# biosignal-daq-v1_0.net
KiCad netlist of a schematic drawn in EAGLE
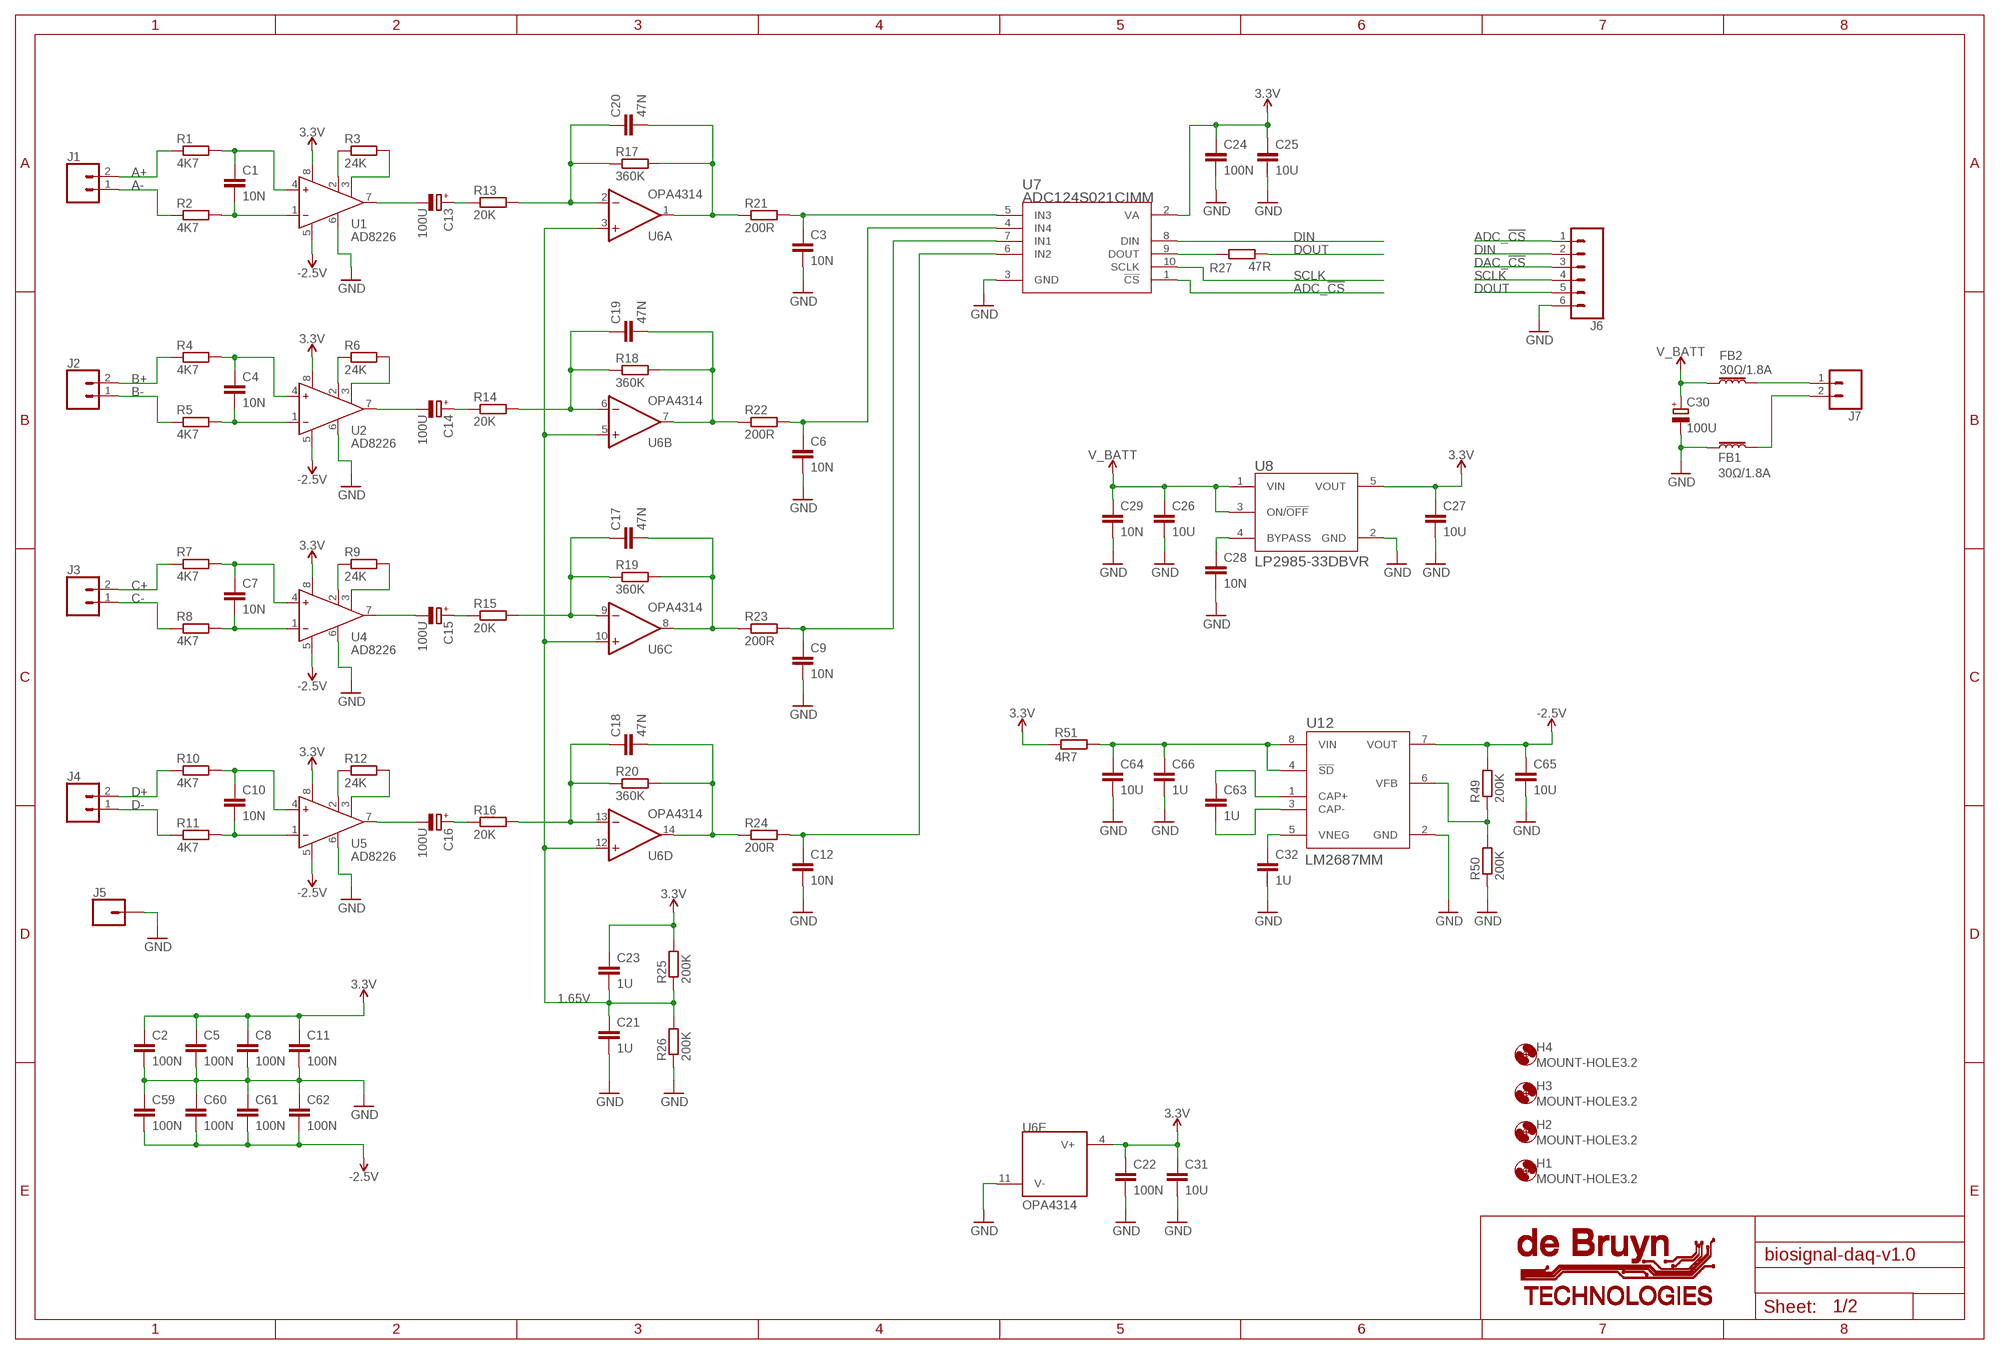
[diagram p0: schematic, sheet 1]
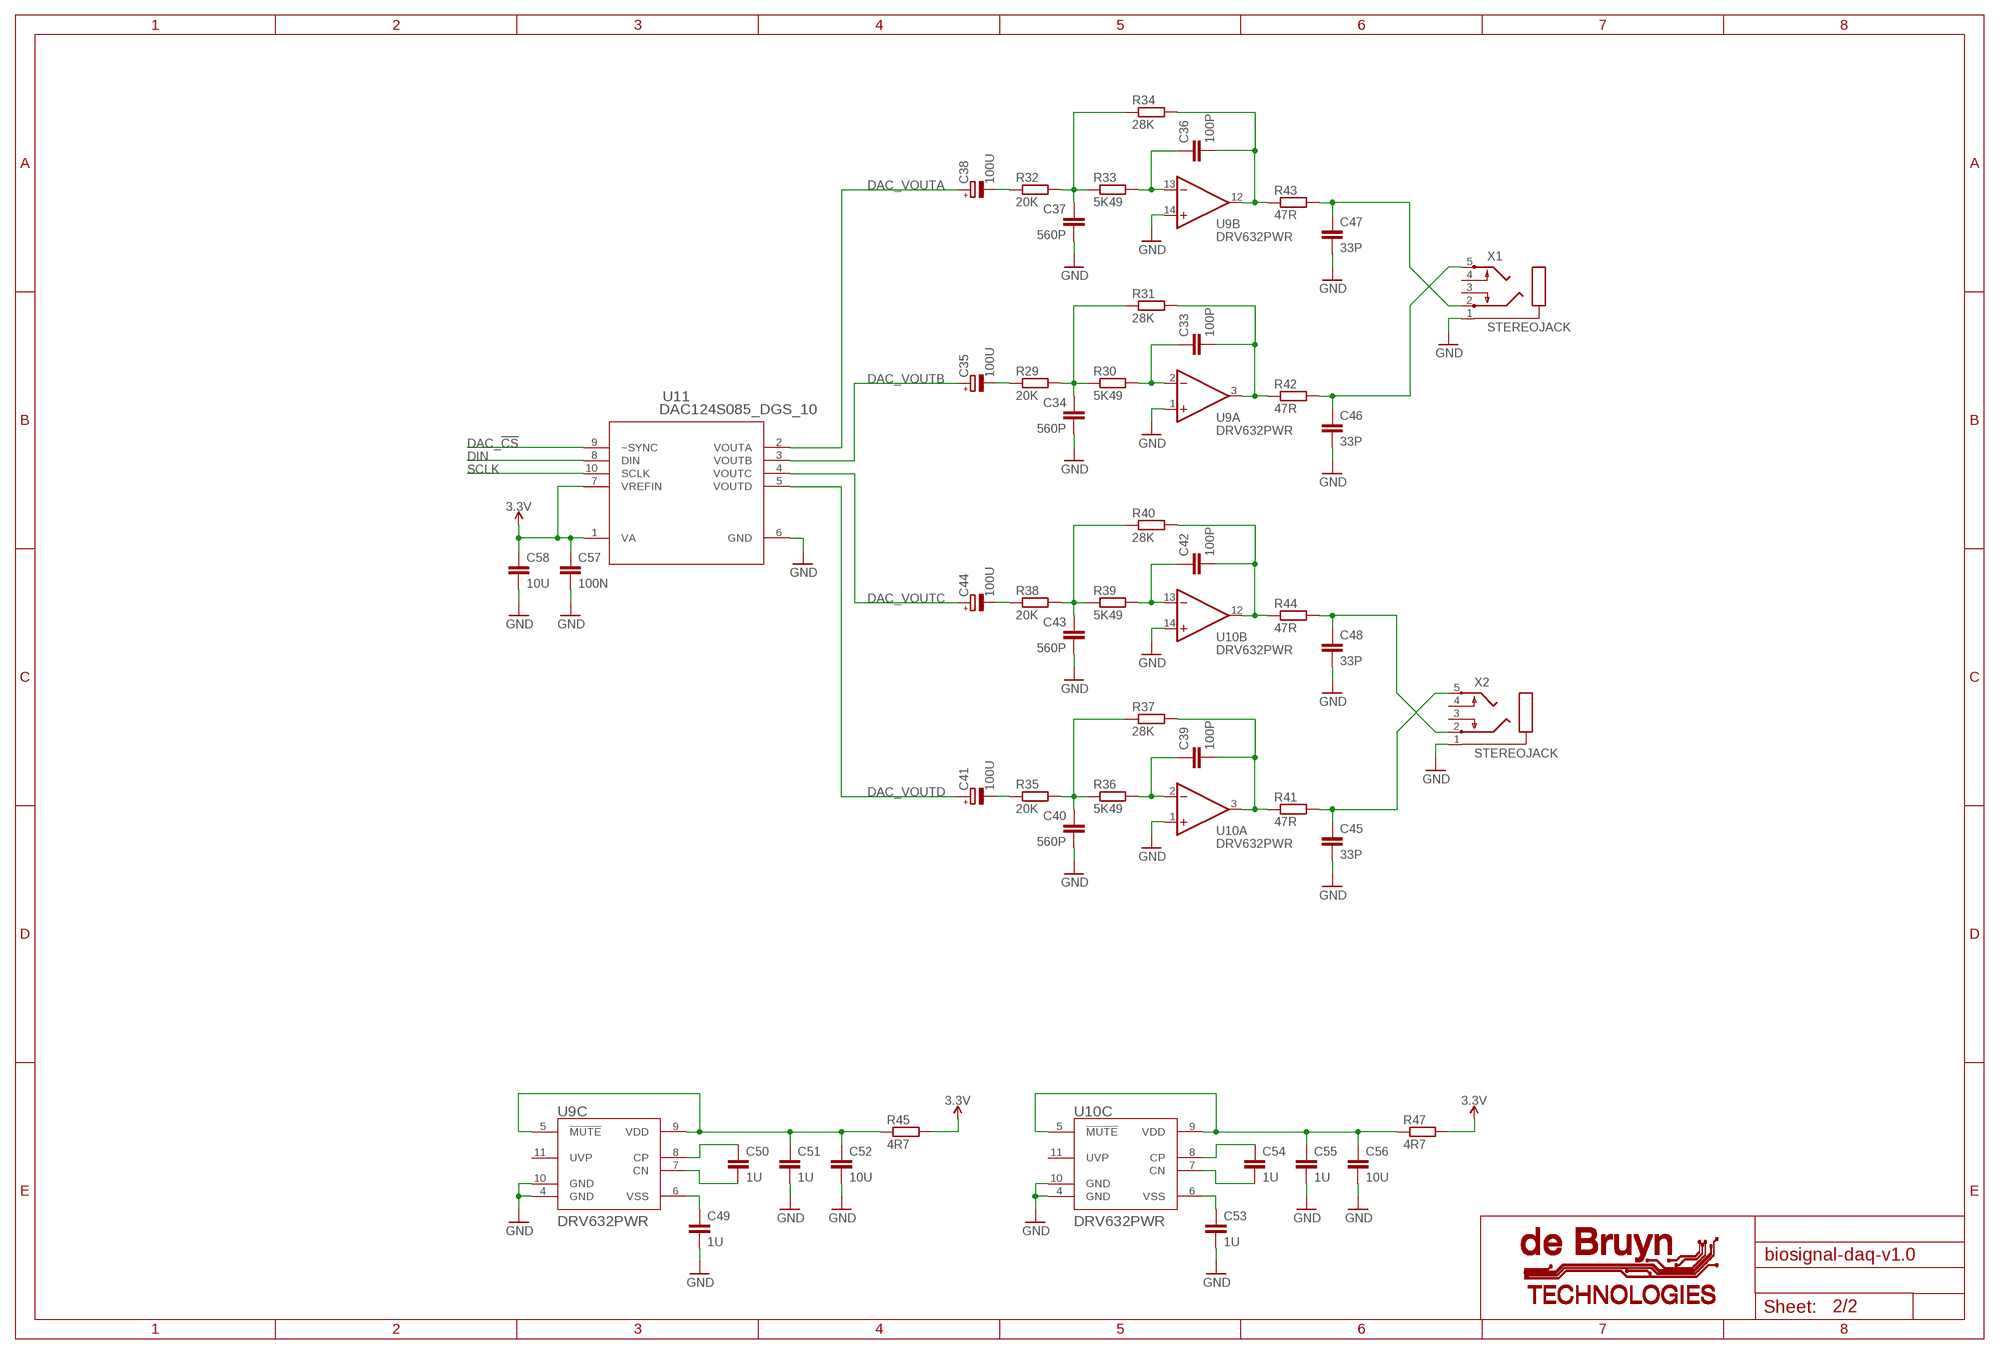
[diagram p1: schematic, sheet 2]

(export (version "E")
  (design (tool "Eeschema 10.0.6"))
  (components
    (comp (ref "C1")
      (value "10N")
      (footprint "eagle-import:CAPC160X80X91L36N")
      (libsource (lib "eagle-import") (part "C0603"))
    )
    (comp (ref "C2")
      (value "100N")
      (footprint "eagle-import:CAPC160X80X91L36N")
      (fields (field (name "MANUFACTURER_PART_NUMBER") "MC0603B104K100CT") (field (name "TOLERANCE") "10%"))
      (libsource (lib "eagle-import") (part "C0603"))
    )
    (comp (ref "C3")
      (value "10N")
      (footprint "eagle-import:CAPC160X80X91L36N")
      (libsource (lib "eagle-import") (part "C0603"))
    )
    (comp (ref "C4")
      (value "10N")
      (footprint "eagle-import:CAPC160X80X91L36N")
      (libsource (lib "eagle-import") (part "C0603"))
    )
    (comp (ref "C5")
      (value "100N")
      (footprint "eagle-import:CAPC160X80X91L36N")
      (fields (field (name "MANUFACTURER_PART_NUMBER") "MC0603B104K100CT") (field (name "TOLERANCE") "10%"))
      (libsource (lib "eagle-import") (part "C0603"))
    )
    (comp (ref "C6")
      (value "10N")
      (footprint "eagle-import:CAPC160X80X91L36N")
      (libsource (lib "eagle-import") (part "C0603"))
    )
    (comp (ref "C7")
      (value "10N")
      (footprint "eagle-import:CAPC160X80X91L36N")
      (libsource (lib "eagle-import") (part "C0603"))
    )
    (comp (ref "C8")
      (value "100N")
      (footprint "eagle-import:CAPC160X80X91L36N")
      (fields (field (name "MANUFACTURER_PART_NUMBER") "MC0603B104K100CT") (field (name "TOLERANCE") "10%"))
      (libsource (lib "eagle-import") (part "C0603"))
    )
    (comp (ref "C9")
      (value "10N")
      (footprint "eagle-import:CAPC160X80X91L36N")
      (libsource (lib "eagle-import") (part "C0603"))
    )
    (comp (ref "C10")
      (value "10N")
      (footprint "eagle-import:CAPC160X80X91L36N")
      (libsource (lib "eagle-import") (part "C0603"))
    )
    (comp (ref "C11")
      (value "100N")
      (footprint "eagle-import:CAPC160X80X91L36N")
      (fields (field (name "MANUFACTURER_PART_NUMBER") "MC0603B104K100CT") (field (name "TOLERANCE") "10%"))
      (libsource (lib "eagle-import") (part "C0603"))
    )
    (comp (ref "C12")
      (value "10N")
      (footprint "eagle-import:CAPC160X80X91L36N")
      (libsource (lib "eagle-import") (part "C0603"))
    )
    (comp (ref "C13")
      (value "100U")
      (footprint "eagle-import:E2-5")
      (libsource (lib "eagle-import") (part "CPOL-EUE2-5"))
    )
    (comp (ref "C14")
      (value "100U")
      (footprint "eagle-import:E2-5")
      (libsource (lib "eagle-import") (part "CPOL-EUE2-5"))
    )
    (comp (ref "C15")
      (value "100U")
      (footprint "eagle-import:E2-5")
      (libsource (lib "eagle-import") (part "CPOL-EUE2-5"))
    )
    (comp (ref "C16")
      (value "100U")
      (footprint "eagle-import:E2-5")
      (libsource (lib "eagle-import") (part "CPOL-EUE2-5"))
    )
    (comp (ref "C17")
      (value "47N")
      (footprint "eagle-import:CAPC200X125X80L50N")
      (libsource (lib "eagle-import") (part "C0805"))
    )
    (comp (ref "C18")
      (value "47N")
      (footprint "eagle-import:CAPC200X125X80L50N")
      (libsource (lib "eagle-import") (part "C0805"))
    )
    (comp (ref "C19")
      (value "47N")
      (footprint "eagle-import:CAPC200X125X80L50N")
      (libsource (lib "eagle-import") (part "C0805"))
    )
    (comp (ref "C20")
      (value "47N")
      (footprint "eagle-import:CAPC200X125X80L50N")
      (libsource (lib "eagle-import") (part "C0805"))
    )
    (comp (ref "C21")
      (value "1U")
      (footprint "eagle-import:CAPC160X80X91L36N")
      (libsource (lib "eagle-import") (part "C0603"))
    )
    (comp (ref "C22")
      (value "100N")
      (footprint "eagle-import:CAPC160X80X91L36N")
      (fields (field (name "MANUFACTURER_PART_NUMBER") "MC0603B104K100CT") (field (name "TOLERANCE") "10%"))
      (libsource (lib "eagle-import") (part "C0603"))
    )
    (comp (ref "C23")
      (value "1U")
      (footprint "eagle-import:CAPC160X80X91L36N")
      (libsource (lib "eagle-import") (part "C0603"))
    )
    (comp (ref "C24")
      (value "100N")
      (footprint "eagle-import:CAPC160X80X91L36N")
      (fields (field (name "MANUFACTURER_PART_NUMBER") "MC0603B104K100CT") (field (name "TOLERANCE") "10%"))
      (libsource (lib "eagle-import") (part "C0603"))
    )
    (comp (ref "C25")
      (value "10U")
      (footprint "eagle-import:CAPC200X125X80L50N")
      (libsource (lib "eagle-import") (part "C0805"))
    )
    (comp (ref "C26")
      (value "10U")
      (footprint "eagle-import:CAPC200X125X80L50N")
      (libsource (lib "eagle-import") (part "C0805"))
    )
    (comp (ref "C27")
      (value "10U")
      (footprint "eagle-import:CAPC200X125X80L50N")
      (libsource (lib "eagle-import") (part "C0805"))
    )
    (comp (ref "C28")
      (value "10N")
      (footprint "eagle-import:CAPC160X80X91L36N")
      (libsource (lib "eagle-import") (part "C0603"))
    )
    (comp (ref "C29")
      (value "10N")
      (footprint "eagle-import:CAPC160X80X91L36N")
      (libsource (lib "eagle-import") (part "C0603"))
    )
    (comp (ref "C30")
      (value "100U")
      (footprint "eagle-import:E2-5")
      (libsource (lib "eagle-import") (part "CPOL-EUE2-5"))
    )
    (comp (ref "C31")
      (value "10U")
      (footprint "eagle-import:CAPC200X125X80L50N")
      (libsource (lib "eagle-import") (part "C0805"))
    )
    (comp (ref "C32")
      (value "1U")
      (footprint "eagle-import:CAPC160X80X91L36N")
      (libsource (lib "eagle-import") (part "C0603"))
    )
    (comp (ref "C59")
      (value "100N")
      (footprint "eagle-import:CAPC160X80X91L36N")
      (fields (field (name "MANUFACTURER_PART_NUMBER") "MC0603B104K100CT") (field (name "TOLERANCE") "10%"))
      (libsource (lib "eagle-import") (part "C0603"))
    )
    (comp (ref "C60")
      (value "100N")
      (footprint "eagle-import:CAPC160X80X91L36N")
      (fields (field (name "MANUFACTURER_PART_NUMBER") "MC0603B104K100CT") (field (name "TOLERANCE") "10%"))
      (libsource (lib "eagle-import") (part "C0603"))
    )
    (comp (ref "C61")
      (value "100N")
      (footprint "eagle-import:CAPC160X80X91L36N")
      (fields (field (name "MANUFACTURER_PART_NUMBER") "MC0603B104K100CT") (field (name "TOLERANCE") "10%"))
      (libsource (lib "eagle-import") (part "C0603"))
    )
    (comp (ref "C62")
      (value "100N")
      (footprint "eagle-import:CAPC160X80X91L36N")
      (fields (field (name "MANUFACTURER_PART_NUMBER") "MC0603B104K100CT") (field (name "TOLERANCE") "10%"))
      (libsource (lib "eagle-import") (part "C0603"))
    )
    (comp (ref "C63")
      (value "1U")
      (footprint "eagle-import:CAPC160X80X91L36N")
      (libsource (lib "eagle-import") (part "C0603"))
    )
    (comp (ref "C64")
      (value "10U")
      (footprint "eagle-import:CAPC200X125X80L50N")
      (libsource (lib "eagle-import") (part "C0805"))
    )
    (comp (ref "C65")
      (value "10U")
      (footprint "eagle-import:CAPC200X125X80L50N")
      (libsource (lib "eagle-import") (part "C0805"))
    )
    (comp (ref "C66")
      (value "1U")
      (footprint "eagle-import:CAPC160X80X91L36N")
      (libsource (lib "eagle-import") (part "C0603"))
    )
    (comp (ref "FB1")
      (value "30Ω/1.8A")
      (footprint "eagle-import:0603")
      (libsource (lib "eagle-import") (part "FERRITE_BEAD-0603"))
    )
    (comp (ref "FB2")
      (value "30Ω/1.8A")
      (footprint "eagle-import:0603")
      (libsource (lib "eagle-import") (part "FERRITE_BEAD-0603"))
    )
    (comp (ref "H1")
      (value "MOUNT-HOLE3.2")
      (footprint "eagle-import:3,2")
      (libsource (lib "eagle-import") (part "MOUNT-HOLE3.2"))
    )
    (comp (ref "H2")
      (value "MOUNT-HOLE3.2")
      (footprint "eagle-import:3,2")
      (libsource (lib "eagle-import") (part "MOUNT-HOLE3.2"))
    )
    (comp (ref "H3")
      (value "MOUNT-HOLE3.2")
      (footprint "eagle-import:3,2")
      (libsource (lib "eagle-import") (part "MOUNT-HOLE3.2"))
    )
    (comp (ref "H4")
      (value "MOUNT-HOLE3.2")
      (footprint "eagle-import:3,2")
      (libsource (lib "eagle-import") (part "MOUNT-HOLE3.2"))
    )
    (comp (ref "J1")
      (value "CONN_021X02_NO_SILK")
      (footprint "eagle-import:1X02_NO_SILK")
      (libsource (lib "eagle-import") (part "CONN_021X02_NO_SILK"))
    )
    (comp (ref "J2")
      (value "CONN_021X02_NO_SILK")
      (footprint "eagle-import:1X02_NO_SILK")
      (libsource (lib "eagle-import") (part "CONN_021X02_NO_SILK"))
    )
    (comp (ref "J3")
      (value "CONN_021X02_NO_SILK")
      (footprint "eagle-import:1X02_NO_SILK")
      (libsource (lib "eagle-import") (part "CONN_021X02_NO_SILK"))
    )
    (comp (ref "J4")
      (value "CONN_021X02_NO_SILK")
      (footprint "eagle-import:1X02_NO_SILK")
      (libsource (lib "eagle-import") (part "CONN_021X02_NO_SILK"))
    )
    (comp (ref "J5")
      (value "CONN_01")
      (footprint "eagle-import:1X01")
      (libsource (lib "eagle-import") (part "CONN_01"))
    )
    (comp (ref "J6")
      (value "CONN_06NO_SILK_NO_POP")
      (footprint "eagle-import:1X06_NO_SILK")
      (libsource (lib "eagle-import") (part "CONN_06NO_SILK_NO_POP"))
    )
    (comp (ref "J7")
      (value "CONN_021X02_NO_SILK")
      (footprint "eagle-import:1X02_NO_SILK")
      (libsource (lib "eagle-import") (part "CONN_021X02_NO_SILK"))
    )
    (comp (ref "R1")
      (value "4K7")
      (footprint "eagle-import:RESC160X80X55L25N")
      (fields (field (name "TOLERANCE") "1%"))
      (libsource (lib "eagle-import") (part "R0603"))
    )
    (comp (ref "R2")
      (value "4K7")
      (footprint "eagle-import:RESC160X80X55L25N")
      (fields (field (name "TOLERANCE") "1%"))
      (libsource (lib "eagle-import") (part "R0603"))
    )
    (comp (ref "R3")
      (value "24K")
      (footprint "eagle-import:RESC160X80X55L25N")
      (fields (field (name "TOLERANCE") "1%"))
      (libsource (lib "eagle-import") (part "R0603"))
    )
    (comp (ref "R4")
      (value "4K7")
      (footprint "eagle-import:RESC160X80X55L25N")
      (fields (field (name "TOLERANCE") "1%"))
      (libsource (lib "eagle-import") (part "R0603"))
    )
    (comp (ref "R5")
      (value "4K7")
      (footprint "eagle-import:RESC160X80X55L25N")
      (libsource (lib "eagle-import") (part "R0603"))
    )
    (comp (ref "R6")
      (value "24K")
      (footprint "eagle-import:RESC160X80X55L25N")
      (libsource (lib "eagle-import") (part "R0603"))
    )
    (comp (ref "R7")
      (value "4K7")
      (footprint "eagle-import:RESC160X80X55L25N")
      (libsource (lib "eagle-import") (part "R0603"))
    )
    (comp (ref "R8")
      (value "4K7")
      (footprint "eagle-import:RESC160X80X55L25N")
      (libsource (lib "eagle-import") (part "R0603"))
    )
    (comp (ref "R9")
      (value "24K")
      (footprint "eagle-import:RESC160X80X55L25N")
      (libsource (lib "eagle-import") (part "R0603"))
    )
    (comp (ref "R10")
      (value "4K7")
      (footprint "eagle-import:RESC160X80X55L25N")
      (libsource (lib "eagle-import") (part "R0603"))
    )
    (comp (ref "R11")
      (value "4K7")
      (footprint "eagle-import:RESC160X80X55L25N")
      (libsource (lib "eagle-import") (part "R0603"))
    )
    (comp (ref "R12")
      (value "24K")
      (footprint "eagle-import:RESC160X80X55L25N")
      (libsource (lib "eagle-import") (part "R0603"))
    )
    (comp (ref "R13")
      (value "20K")
      (footprint "eagle-import:RESC160X80X55L25N")
      (libsource (lib "eagle-import") (part "R0603"))
    )
    (comp (ref "R14")
      (value "20K")
      (footprint "eagle-import:RESC160X80X55L25N")
      (libsource (lib "eagle-import") (part "R0603"))
    )
    (comp (ref "R15")
      (value "20K")
      (footprint "eagle-import:RESC160X80X55L25N")
      (libsource (lib "eagle-import") (part "R0603"))
    )
    (comp (ref "R16")
      (value "20K")
      (footprint "eagle-import:RESC160X80X55L25N")
      (libsource (lib "eagle-import") (part "R0603"))
    )
    (comp (ref "R17")
      (value "360K")
      (footprint "eagle-import:RESC160X80X55L25N")
      (libsource (lib "eagle-import") (part "R0603"))
    )
    (comp (ref "R18")
      (value "360K")
      (footprint "eagle-import:RESC160X80X55L25N")
      (libsource (lib "eagle-import") (part "R0603"))
    )
    (comp (ref "R19")
      (value "360K")
      (footprint "eagle-import:RESC160X80X55L25N")
      (libsource (lib "eagle-import") (part "R0603"))
    )
    (comp (ref "R20")
      (value "360K")
      (footprint "eagle-import:RESC160X80X55L25N")
      (libsource (lib "eagle-import") (part "R0603"))
    )
    (comp (ref "R21")
      (value "200R")
      (footprint "eagle-import:RESC160X80X55L25N")
      (libsource (lib "eagle-import") (part "R0603"))
    )
    (comp (ref "R22")
      (value "200R")
      (footprint "eagle-import:RESC160X80X55L25N")
      (libsource (lib "eagle-import") (part "R0603"))
    )
    (comp (ref "R23")
      (value "200R")
      (footprint "eagle-import:RESC160X80X55L25N")
      (libsource (lib "eagle-import") (part "R0603"))
    )
    (comp (ref "R24")
      (value "200R")
      (footprint "eagle-import:RESC160X80X55L25N")
      (libsource (lib "eagle-import") (part "R0603"))
    )
    (comp (ref "R25")
      (value "200K")
      (footprint "eagle-import:RESC160X80X55L25N")
      (libsource (lib "eagle-import") (part "R0603"))
    )
    (comp (ref "R26")
      (value "200K")
      (footprint "eagle-import:RESC160X80X55L25N")
      (libsource (lib "eagle-import") (part "R0603"))
    )
    (comp (ref "R27")
      (value "47R")
      (footprint "eagle-import:RESC160X80X55L25N")
      (libsource (lib "eagle-import") (part "R0603"))
    )
    (comp (ref "R49")
      (value "200K")
      (footprint "eagle-import:RESC160X80X55L25N")
      (libsource (lib "eagle-import") (part "R0603"))
    )
    (comp (ref "R50")
      (value "200K")
      (footprint "eagle-import:RESC160X80X55L25N")
      (libsource (lib "eagle-import") (part "R0603"))
    )
    (comp (ref "R51")
      (value "4R7")
      (footprint "eagle-import:RESC160X80X55L25N")
      (libsource (lib "eagle-import") (part "R0603"))
    )
    (comp (ref "U1")
      (value "AD8226")
      (footprint "eagle-import:SOP8P65_300X490X95L60X32N")
      (libsource (lib "eagle-import") (part "AD8226"))
    )
    (comp (ref "U2")
      (value "AD8226")
      (footprint "eagle-import:SOP8P65_300X490X95L60X32N")
      (libsource (lib "eagle-import") (part "AD8226"))
    )
    (comp (ref "U4")
      (value "AD8226")
      (footprint "eagle-import:SOP8P65_300X490X95L60X32N")
      (libsource (lib "eagle-import") (part "AD8226"))
    )
    (comp (ref "U5")
      (value "AD8226")
      (footprint "eagle-import:SOP8P65_300X490X95L60X32N")
      (libsource (lib "eagle-import") (part "AD8226"))
    )
    (comp (ref "U6")
      (value "OPA4314")
      (footprint "eagle-import:PW14")
      (libsource (lib "eagle-import") (part "OPA4314"))
    )
    (comp (ref "U7")
      (value "ADC124S021CIMM")
      (footprint "eagle-import:MUB10A")
      (libsource (lib "eagle-import") (part "ADC124S021CIMM"))
    )
    (comp (ref "U8")
      (value "LP2985-33DBVR")
      (footprint "eagle-import:DBV5")
      (fields (field (name "MANUFACTURER_PART_NUMBER") "LP298533DBVR"))
      (libsource (lib "eagle-import") (part "LP2985-33DBVR"))
    )
    (comp (ref "U12")
      (value "LM2687MM")
      (footprint "eagle-import:MUA08A")
      (libsource (lib "eagle-import") (part "LM2687MM"))
    )
    (comp (ref "C33")
      (value "100P")
      (footprint "eagle-import:CAPC160X80X91L36N")
      (libsource (lib "eagle-import") (part "C0603"))
    )
    (comp (ref "C34")
      (value "560P")
      (footprint "eagle-import:CAPC160X80X91L36N")
      (libsource (lib "eagle-import") (part "C0603"))
    )
    (comp (ref "C35")
      (value "100U")
      (footprint "eagle-import:E2-5")
      (libsource (lib "eagle-import") (part "CPOL-EUE2-5"))
    )
    (comp (ref "C36")
      (value "100P")
      (footprint "eagle-import:CAPC160X80X91L36N")
      (libsource (lib "eagle-import") (part "C0603"))
    )
    (comp (ref "C37")
      (value "560P")
      (footprint "eagle-import:CAPC160X80X91L36N")
      (libsource (lib "eagle-import") (part "C0603"))
    )
    (comp (ref "C38")
      (value "100U")
      (footprint "eagle-import:E2-5")
      (libsource (lib "eagle-import") (part "CPOL-EUE2-5"))
    )
    (comp (ref "C39")
      (value "100P")
      (footprint "eagle-import:CAPC160X80X91L36N")
      (libsource (lib "eagle-import") (part "C0603"))
    )
    (comp (ref "C40")
      (value "560P")
      (footprint "eagle-import:CAPC160X80X91L36N")
      (libsource (lib "eagle-import") (part "C0603"))
    )
    (comp (ref "C41")
      (value "100U")
      (footprint "eagle-import:E2-5")
      (libsource (lib "eagle-import") (part "CPOL-EUE2-5"))
    )
    (comp (ref "C42")
      (value "100P")
      (footprint "eagle-import:CAPC160X80X91L36N")
      (libsource (lib "eagle-import") (part "C0603"))
    )
    (comp (ref "C43")
      (value "560P")
      (footprint "eagle-import:CAPC160X80X91L36N")
      (libsource (lib "eagle-import") (part "C0603"))
    )
    (comp (ref "C44")
      (value "100U")
      (footprint "eagle-import:E2-5")
      (libsource (lib "eagle-import") (part "CPOL-EUE2-5"))
    )
    (comp (ref "C45")
      (value "33P")
      (footprint "eagle-import:CAPC160X80X91L36N")
      (libsource (lib "eagle-import") (part "C0603"))
    )
    (comp (ref "C46")
      (value "33P")
      (footprint "eagle-import:CAPC160X80X91L36N")
      (libsource (lib "eagle-import") (part "C0603"))
    )
    (comp (ref "C47")
      (value "33P")
      (footprint "eagle-import:CAPC160X80X91L36N")
      (libsource (lib "eagle-import") (part "C0603"))
    )
    (comp (ref "C48")
      (value "33P")
      (footprint "eagle-import:CAPC160X80X91L36N")
      (libsource (lib "eagle-import") (part "C0603"))
    )
    (comp (ref "C49")
      (value "1U")
      (footprint "eagle-import:CAPC160X80X91L36N")
      (libsource (lib "eagle-import") (part "C0603"))
    )
    (comp (ref "C50")
      (value "1U")
      (footprint "eagle-import:CAPC160X80X91L36N")
      (libsource (lib "eagle-import") (part "C0603"))
    )
    (comp (ref "C51")
      (value "1U")
      (footprint "eagle-import:CAPC160X80X91L36N")
      (libsource (lib "eagle-import") (part "C0603"))
    )
    (comp (ref "C52")
      (value "10U")
      (footprint "eagle-import:CAPC200X125X80L50N")
      (libsource (lib "eagle-import") (part "C0805"))
    )
    (comp (ref "C53")
      (value "1U")
      (footprint "eagle-import:CAPC160X80X91L36N")
      (libsource (lib "eagle-import") (part "C0603"))
    )
    (comp (ref "C54")
      (value "1U")
      (footprint "eagle-import:CAPC160X80X91L36N")
      (libsource (lib "eagle-import") (part "C0603"))
    )
    (comp (ref "C55")
      (value "1U")
      (footprint "eagle-import:CAPC160X80X91L36N")
      (libsource (lib "eagle-import") (part "C0603"))
    )
    (comp (ref "C56")
      (value "10U")
      (footprint "eagle-import:CAPC200X125X80L50N")
      (libsource (lib "eagle-import") (part "C0805"))
    )
    (comp (ref "C57")
      (value "100N")
      (footprint "eagle-import:CAPC160X80X91L36N")
      (libsource (lib "eagle-import") (part "C0603"))
    )
    (comp (ref "C58")
      (value "10U")
      (footprint "eagle-import:CAPC200X125X80L50N")
      (libsource (lib "eagle-import") (part "C0805"))
    )
    (comp (ref "R29")
      (value "20K")
      (footprint "eagle-import:RESC160X80X55L25N")
      (libsource (lib "eagle-import") (part "R0603"))
    )
    (comp (ref "R30")
      (value "5K49")
      (footprint "eagle-import:RESC160X80X55L25N")
      (libsource (lib "eagle-import") (part "R0603"))
    )
    (comp (ref "R31")
      (value "28K")
      (footprint "eagle-import:RESC160X80X55L25N")
      (libsource (lib "eagle-import") (part "R0603"))
    )
    (comp (ref "R32")
      (value "20K")
      (footprint "eagle-import:RESC160X80X55L25N")
      (libsource (lib "eagle-import") (part "R0603"))
    )
    (comp (ref "R33")
      (value "5K49")
      (footprint "eagle-import:RESC160X80X55L25N")
      (libsource (lib "eagle-import") (part "R0603"))
    )
    (comp (ref "R34")
      (value "28K")
      (footprint "eagle-import:RESC160X80X55L25N")
      (libsource (lib "eagle-import") (part "R0603"))
    )
    (comp (ref "R35")
      (value "20K")
      (footprint "eagle-import:RESC160X80X55L25N")
      (libsource (lib "eagle-import") (part "R0603"))
    )
    (comp (ref "R36")
      (value "5K49")
      (footprint "eagle-import:RESC160X80X55L25N")
      (libsource (lib "eagle-import") (part "R0603"))
    )
    (comp (ref "R37")
      (value "28K")
      (footprint "eagle-import:RESC160X80X55L25N")
      (libsource (lib "eagle-import") (part "R0603"))
    )
    (comp (ref "R38")
      (value "20K")
      (footprint "eagle-import:RESC160X80X55L25N")
      (libsource (lib "eagle-import") (part "R0603"))
    )
    (comp (ref "R39")
      (value "5K49")
      (footprint "eagle-import:RESC160X80X55L25N")
      (libsource (lib "eagle-import") (part "R0603"))
    )
    (comp (ref "R40")
      (value "28K")
      (footprint "eagle-import:RESC160X80X55L25N")
      (libsource (lib "eagle-import") (part "R0603"))
    )
    (comp (ref "R41")
      (value "47R")
      (footprint "eagle-import:RESC160X80X55L25N")
      (libsource (lib "eagle-import") (part "R0603"))
    )
    (comp (ref "R42")
      (value "47R")
      (footprint "eagle-import:RESC160X80X55L25N")
      (libsource (lib "eagle-import") (part "R0603"))
    )
    (comp (ref "R43")
      (value "47R")
      (footprint "eagle-import:RESC160X80X55L25N")
      (libsource (lib "eagle-import") (part "R0603"))
    )
    (comp (ref "R44")
      (value "47R")
      (footprint "eagle-import:RESC160X80X55L25N")
      (libsource (lib "eagle-import") (part "R0603"))
    )
    (comp (ref "R45")
      (value "4R7")
      (footprint "eagle-import:RESC160X80X55L25N")
      (libsource (lib "eagle-import") (part "R0603"))
    )
    (comp (ref "R47")
      (value "4R7")
      (footprint "eagle-import:RESC160X80X55L25N")
      (libsource (lib "eagle-import") (part "R0603"))
    )
    (comp (ref "U9")
      (value "DRV632PWR")
      (footprint "eagle-import:PW14")
      (libsource (lib "eagle-import") (part "DRV632PWR"))
    )
    (comp (ref "U10")
      (value "DRV632PWR")
      (footprint "eagle-import:PW14")
      (libsource (lib "eagle-import") (part "DRV632PWR"))
    )
    (comp (ref "U11")
      (value "DAC124S085_DGS_10")
      (footprint "eagle-import:MUB10A")
      (libsource (lib "eagle-import") (part "DAC124S085_DGS_10"))
    )
    (comp (ref "X1")
      (value "STEREOJACK")
      (footprint "eagle-import:STX3100")
      (libsource (lib "eagle-import") (part "STEREOJACK"))
    )
    (comp (ref "X2")
      (value "STEREOJACK")
      (footprint "eagle-import:STX3100")
      (libsource (lib "eagle-import") (part "STEREOJACK"))
    )
  )
  (nets
    (net (code "1") (name "-2.5V") (class "Default")
      (node (ref "C59") (pin "2") (pinfunction "2_2") (pintype "passive"))
      (node (ref "C60") (pin "2") (pinfunction "2_2") (pintype "passive"))
      (node (ref "C61") (pin "2") (pinfunction "2_2") (pintype "passive"))
      (node (ref "C62") (pin "2") (pinfunction "2_2") (pintype "passive"))
      (node (ref "C65") (pin "1") (pinfunction "1_1") (pintype "passive"))
      (node (ref "R49") (pin "2") (pinfunction "2_2") (pintype "passive"))
      (node (ref "U1") (pin "5") (pinfunction "-VS_5") (pintype "power_in"))
      (node (ref "U12") (pin "7") (pinfunction "VOUT_7") (pintype "output"))
      (node (ref "U2") (pin "5") (pinfunction "-VS_5") (pintype "power_in"))
      (node (ref "U4") (pin "5") (pinfunction "-VS_5") (pintype "power_in"))
      (node (ref "U5") (pin "5") (pinfunction "-VS_5") (pintype "power_in"))
    )
    (net (code "2") (name "1.65V") (class "Default")
      (node (ref "C21") (pin "1") (pinfunction "1_1") (pintype "passive"))
      (node (ref "C23") (pin "2") (pinfunction "2_2") (pintype "passive"))
      (node (ref "R25") (pin "1") (pinfunction "1_1") (pintype "passive"))
      (node (ref "R26") (pin "2") (pinfunction "2_2") (pintype "passive"))
      (node (ref "U6") (pin "10") (pinfunction "+IN_10") (pintype "input"))
      (node (ref "U6") (pin "12") (pinfunction "+IN_12") (pintype "input"))
      (node (ref "U6") (pin "3") (pinfunction "+IN_3") (pintype "input"))
      (node (ref "U6") (pin "5") (pinfunction "+IN_5") (pintype "input"))
    )
    (net (code "3") (name "3.3V") (class "Default")
      (node (ref "C11") (pin "1") (pinfunction "1_1") (pintype "passive"))
      (node (ref "C2") (pin "1") (pinfunction "1_1") (pintype "passive"))
      (node (ref "C22") (pin "1") (pinfunction "1_1") (pintype "passive"))
      (node (ref "C23") (pin "1") (pinfunction "1_1") (pintype "passive"))
      (node (ref "C24") (pin "1") (pinfunction "1_1") (pintype "passive"))
      (node (ref "C25") (pin "1") (pinfunction "1_1") (pintype "passive"))
      (node (ref "C27") (pin "1") (pinfunction "1_1") (pintype "passive"))
      (node (ref "C31") (pin "1") (pinfunction "1_1") (pintype "passive"))
      (node (ref "C5") (pin "1") (pinfunction "1_1") (pintype "passive"))
      (node (ref "C57") (pin "1") (pinfunction "1_1") (pintype "passive"))
      (node (ref "C58") (pin "1") (pinfunction "1_1") (pintype "passive"))
      (node (ref "C8") (pin "1") (pinfunction "1_1") (pintype "passive"))
      (node (ref "R25") (pin "2") (pinfunction "2_2") (pintype "passive"))
      (node (ref "R45") (pin "2") (pinfunction "2_2") (pintype "passive"))
      (node (ref "R47") (pin "2") (pinfunction "2_2") (pintype "passive"))
      (node (ref "R51") (pin "1") (pinfunction "1_1") (pintype "passive"))
      (node (ref "U1") (pin "8") (pinfunction "+VS_8") (pintype "power_in"))
      (node (ref "U11") (pin "1") (pinfunction "VA_1") (pintype "power_in"))
      (node (ref "U11") (pin "7") (pinfunction "VREFIN_7") (pintype "input"))
      (node (ref "U2") (pin "8") (pinfunction "+VS_8") (pintype "power_in"))
      (node (ref "U4") (pin "8") (pinfunction "+VS_8") (pintype "power_in"))
      (node (ref "U5") (pin "8") (pinfunction "+VS_8") (pintype "power_in"))
      (node (ref "U6") (pin "4") (pinfunction "V+_4") (pintype "power_in"))
      (node (ref "U7") (pin "2") (pinfunction "VA_2") (pintype "passive"))
      (node (ref "U8") (pin "5") (pinfunction "VOUT_5") (pintype "output"))
    )
    (net (code "4") (name "A+") (class "Default")
      (node (ref "J1") (pin "2") (pinfunction "2_2") (pintype "passive"))
      (node (ref "R1") (pin "1") (pinfunction "1_1") (pintype "passive"))
    )
    (net (code "5") (name "A-") (class "Default")
      (node (ref "J1") (pin "1") (pinfunction "1_1") (pintype "passive"))
      (node (ref "R2") (pin "1") (pinfunction "1_1") (pintype "passive"))
    )
    (net (code "6") (name "ADC_~{CS}") (class "Default")
      (node (ref "J6") (pin "1") (pinfunction "1_1") (pintype "passive"))
      (node (ref "U7") (pin "1") (pinfunction "~{CS}_1") (pintype "passive"))
    )
    (net (code "7") (name "B+") (class "Default")
      (node (ref "J2") (pin "2") (pinfunction "2_2") (pintype "passive"))
      (node (ref "R4") (pin "1") (pinfunction "1_1") (pintype "passive"))
    )
    (net (code "8") (name "B-") (class "Default")
      (node (ref "J2") (pin "1") (pinfunction "1_1") (pintype "passive"))
      (node (ref "R5") (pin "1") (pinfunction "1_1") (pintype "passive"))
    )
    (net (code "9") (name "C+") (class "Default")
      (node (ref "J3") (pin "2") (pinfunction "2_2") (pintype "passive"))
      (node (ref "R7") (pin "1") (pinfunction "1_1") (pintype "passive"))
    )
    (net (code "10") (name "C-") (class "Default")
      (node (ref "J3") (pin "1") (pinfunction "1_1") (pintype "passive"))
      (node (ref "R8") (pin "1") (pinfunction "1_1") (pintype "passive"))
    )
    (net (code "11") (name "D+") (class "Default")
      (node (ref "J4") (pin "2") (pinfunction "2_2") (pintype "passive"))
      (node (ref "R10") (pin "1") (pinfunction "1_1") (pintype "passive"))
    )
    (net (code "12") (name "D-") (class "Default")
      (node (ref "J4") (pin "1") (pinfunction "1_1") (pintype "passive"))
      (node (ref "R11") (pin "1") (pinfunction "1_1") (pintype "passive"))
    )
    (net (code "13") (name "DAC_VOUTA") (class "Default")
      (node (ref "C38") (pin "+") (pinfunction "+_+") (pintype "passive"))
      (node (ref "U11") (pin "2") (pinfunction "VOUTA_2") (pintype "output"))
    )
    (net (code "14") (name "DAC_VOUTB") (class "Default")
      (node (ref "C35") (pin "+") (pinfunction "+_+") (pintype "passive"))
      (node (ref "U11") (pin "3") (pinfunction "VOUTB_3") (pintype "output"))
    )
    (net (code "15") (name "DAC_VOUTC") (class "Default")
      (node (ref "C44") (pin "+") (pinfunction "+_+") (pintype "passive"))
      (node (ref "U11") (pin "4") (pinfunction "VOUTC_4") (pintype "output"))
    )
    (net (code "16") (name "DAC_VOUTD") (class "Default")
      (node (ref "C41") (pin "+") (pinfunction "+_+") (pintype "passive"))
      (node (ref "U11") (pin "5") (pinfunction "VOUTD_5") (pintype "output"))
    )
    (net (code "17") (name "DAC_~{CS}") (class "Default")
      (node (ref "J6") (pin "3") (pinfunction "3_3") (pintype "passive"))
      (node (ref "U11") (pin "9") (pinfunction "~{SYNC}_9") (pintype "input"))
    )
    (net (code "18") (name "DIN") (class "Default")
      (node (ref "J6") (pin "2") (pinfunction "2_2") (pintype "passive"))
      (node (ref "U11") (pin "8") (pinfunction "DIN_8") (pintype "input"))
      (node (ref "U7") (pin "8") (pinfunction "DIN_8") (pintype "input"))
    )
    (net (code "19") (name "DOUT") (class "Default")
      (node (ref "J6") (pin "5") (pinfunction "5_5") (pintype "passive"))
      (node (ref "R27") (pin "2") (pinfunction "2_2") (pintype "passive"))
    )
    (net (code "20") (name "GND") (class "Default")
      (node (ref "C11") (pin "2") (pinfunction "2_2") (pintype "passive"))
      (node (ref "C12") (pin "2") (pinfunction "2_2") (pintype "passive"))
      (node (ref "C2") (pin "2") (pinfunction "2_2") (pintype "passive"))
      (node (ref "C21") (pin "2") (pinfunction "2_2") (pintype "passive"))
      (node (ref "C22") (pin "2") (pinfunction "2_2") (pintype "passive"))
      (node (ref "C24") (pin "2") (pinfunction "2_2") (pintype "passive"))
      (node (ref "C25") (pin "2") (pinfunction "2_2") (pintype "passive"))
      (node (ref "C26") (pin "2") (pinfunction "2_2") (pintype "passive"))
      (node (ref "C27") (pin "2") (pinfunction "2_2") (pintype "passive"))
      (node (ref "C28") (pin "2") (pinfunction "2_2") (pintype "passive"))
      (node (ref "C29") (pin "2") (pinfunction "2_2") (pintype "passive"))
      (node (ref "C3") (pin "2") (pinfunction "2_2") (pintype "passive"))
      (node (ref "C30") (pin "-") (pinfunction "-_-") (pintype "passive"))
      (node (ref "C31") (pin "2") (pinfunction "2_2") (pintype "passive"))
      (node (ref "C32") (pin "2") (pinfunction "2_2") (pintype "passive"))
      (node (ref "C34") (pin "2") (pinfunction "2_2") (pintype "passive"))
      (node (ref "C37") (pin "2") (pinfunction "2_2") (pintype "passive"))
      (node (ref "C40") (pin "2") (pinfunction "2_2") (pintype "passive"))
      (node (ref "C43") (pin "2") (pinfunction "2_2") (pintype "passive"))
      (node (ref "C45") (pin "2") (pinfunction "2_2") (pintype "passive"))
      (node (ref "C46") (pin "2") (pinfunction "2_2") (pintype "passive"))
      (node (ref "C47") (pin "2") (pinfunction "2_2") (pintype "passive"))
      (node (ref "C48") (pin "2") (pinfunction "2_2") (pintype "passive"))
      (node (ref "C49") (pin "2") (pinfunction "2_2") (pintype "passive"))
      (node (ref "C5") (pin "2") (pinfunction "2_2") (pintype "passive"))
      (node (ref "C51") (pin "2") (pinfunction "2_2") (pintype "passive"))
      (node (ref "C52") (pin "2") (pinfunction "2_2") (pintype "passive"))
      (node (ref "C53") (pin "2") (pinfunction "2_2") (pintype "passive"))
      (node (ref "C55") (pin "2") (pinfunction "2_2") (pintype "passive"))
      (node (ref "C56") (pin "2") (pinfunction "2_2") (pintype "passive"))
      (node (ref "C57") (pin "2") (pinfunction "2_2") (pintype "passive"))
      (node (ref "C58") (pin "2") (pinfunction "2_2") (pintype "passive"))
      (node (ref "C59") (pin "1") (pinfunction "1_1") (pintype "passive"))
      (node (ref "C6") (pin "2") (pinfunction "2_2") (pintype "passive"))
      (node (ref "C60") (pin "1") (pinfunction "1_1") (pintype "passive"))
      (node (ref "C61") (pin "1") (pinfunction "1_1") (pintype "passive"))
      (node (ref "C62") (pin "1") (pinfunction "1_1") (pintype "passive"))
      (node (ref "C64") (pin "2") (pinfunction "2_2") (pintype "passive"))
      (node (ref "C65") (pin "2") (pinfunction "2_2") (pintype "passive"))
      (node (ref "C66") (pin "2") (pinfunction "2_2") (pintype "passive"))
      (node (ref "C8") (pin "2") (pinfunction "2_2") (pintype "passive"))
      (node (ref "C9") (pin "2") (pinfunction "2_2") (pintype "passive"))
      (node (ref "FB1") (pin "1") (pinfunction "1_1") (pintype "passive"))
      (node (ref "J5") (pin "1") (pinfunction "1_1") (pintype "passive"))
      (node (ref "J6") (pin "6") (pinfunction "6_6") (pintype "passive"))
      (node (ref "R26") (pin "1") (pinfunction "1_1") (pintype "passive"))
      (node (ref "R50") (pin "1") (pinfunction "1_1") (pintype "passive"))
      (node (ref "U1") (pin "6") (pinfunction "REF_6") (pintype "passive"))
      (node (ref "U10") (pin "1") (pinfunction "+IN_1") (pintype "input"))
      (node (ref "U10") (pin "10") (pinfunction "GND_10") (pintype "power_in"))
      (node (ref "U10") (pin "14") (pinfunction "+IN_14") (pintype "input"))
      (node (ref "U10") (pin "4") (pinfunction "GND_4") (pintype "power_in"))
      (node (ref "U11") (pin "6") (pinfunction "GND_6") (pintype "power_in"))
      (node (ref "U12") (pin "2") (pinfunction "GND_2") (pintype "passive"))
      (node (ref "U2") (pin "6") (pinfunction "REF_6") (pintype "passive"))
      (node (ref "U4") (pin "6") (pinfunction "REF_6") (pintype "passive"))
      (node (ref "U5") (pin "6") (pinfunction "REF_6") (pintype "passive"))
      (node (ref "U6") (pin "11") (pinfunction "V-_11") (pintype "power_in"))
      (node (ref "U7") (pin "3") (pinfunction "GND_3") (pintype "passive"))
      (node (ref "U8") (pin "2") (pinfunction "GND_2") (pintype "power_in"))
      (node (ref "U9") (pin "1") (pinfunction "+IN_1") (pintype "input"))
      (node (ref "U9") (pin "10") (pinfunction "GND_10") (pintype "power_in"))
      (node (ref "U9") (pin "14") (pinfunction "+IN_14") (pintype "input"))
      (node (ref "U9") (pin "4") (pinfunction "GND_4") (pintype "power_in"))
      (node (ref "X1") (pin "1") (pinfunction "1_1") (pintype "passive"))
      (node (ref "X2") (pin "1") (pinfunction "1_1") (pintype "passive"))
    )
    (net (code "21") (name "Net-(C13-Pad+)") (class "Default")
      (node (ref "C13") (pin "+") (pinfunction "+_+") (pintype "passive"))
      (node (ref "R13") (pin "1") (pinfunction "1_1") (pintype "passive"))
    )
    (net (code "22") (name "Net-(C14-Pad+)") (class "Default")
      (node (ref "C14") (pin "+") (pinfunction "+_+") (pintype "passive"))
      (node (ref "R14") (pin "1") (pinfunction "1_1") (pintype "passive"))
    )
    (net (code "23") (name "Net-(C15-Pad+)") (class "Default")
      (node (ref "C15") (pin "+") (pinfunction "+_+") (pintype "passive"))
      (node (ref "R15") (pin "1") (pinfunction "1_1") (pintype "passive"))
    )
    (net (code "24") (name "Net-(C16-Pad+)") (class "Default")
      (node (ref "C16") (pin "+") (pinfunction "+_+") (pintype "passive"))
      (node (ref "R16") (pin "1") (pinfunction "1_1") (pintype "passive"))
    )
    (net (code "25") (name "Net-(C34-Pad1)") (class "Default")
      (node (ref "C34") (pin "1") (pinfunction "1_1") (pintype "passive"))
      (node (ref "R29") (pin "2") (pinfunction "2_2") (pintype "passive"))
      (node (ref "R30") (pin "1") (pinfunction "1_1") (pintype "passive"))
      (node (ref "R31") (pin "1") (pinfunction "1_1") (pintype "passive"))
    )
    (net (code "26") (name "Net-(C35-Pad-)") (class "Default")
      (node (ref "C35") (pin "-") (pinfunction "-_-") (pintype "passive"))
      (node (ref "R29") (pin "1") (pinfunction "1_1") (pintype "passive"))
    )
    (net (code "27") (name "Net-(C37-Pad1)") (class "Default")
      (node (ref "C37") (pin "1") (pinfunction "1_1") (pintype "passive"))
      (node (ref "R32") (pin "2") (pinfunction "2_2") (pintype "passive"))
      (node (ref "R33") (pin "1") (pinfunction "1_1") (pintype "passive"))
      (node (ref "R34") (pin "1") (pinfunction "1_1") (pintype "passive"))
    )
    (net (code "28") (name "Net-(C38-Pad-)") (class "Default")
      (node (ref "C38") (pin "-") (pinfunction "-_-") (pintype "passive"))
      (node (ref "R32") (pin "1") (pinfunction "1_1") (pintype "passive"))
    )
    (net (code "29") (name "Net-(C40-Pad1)") (class "Default")
      (node (ref "C40") (pin "1") (pinfunction "1_1") (pintype "passive"))
      (node (ref "R35") (pin "2") (pinfunction "2_2") (pintype "passive"))
      (node (ref "R36") (pin "1") (pinfunction "1_1") (pintype "passive"))
      (node (ref "R37") (pin "1") (pinfunction "1_1") (pintype "passive"))
    )
    (net (code "30") (name "Net-(C41-Pad-)") (class "Default")
      (node (ref "C41") (pin "-") (pinfunction "-_-") (pintype "passive"))
      (node (ref "R35") (pin "1") (pinfunction "1_1") (pintype "passive"))
    )
    (net (code "31") (name "Net-(C43-Pad1)") (class "Default")
      (node (ref "C43") (pin "1") (pinfunction "1_1") (pintype "passive"))
      (node (ref "R38") (pin "2") (pinfunction "2_2") (pintype "passive"))
      (node (ref "R39") (pin "1") (pinfunction "1_1") (pintype "passive"))
      (node (ref "R40") (pin "1") (pinfunction "1_1") (pintype "passive"))
    )
    (net (code "32") (name "Net-(C44-Pad-)") (class "Default")
      (node (ref "C44") (pin "-") (pinfunction "-_-") (pintype "passive"))
      (node (ref "R38") (pin "1") (pinfunction "1_1") (pintype "passive"))
    )
    (net (code "33") (name "Net-(C45-Pad1)") (class "Default")
      (node (ref "C45") (pin "1") (pinfunction "1_1") (pintype "passive"))
      (node (ref "R41") (pin "2") (pinfunction "2_2") (pintype "passive"))
      (node (ref "X2") (pin "5") (pinfunction "5_5") (pintype "passive"))
    )
    (net (code "34") (name "Net-(C46-Pad1)") (class "Default")
      (node (ref "C46") (pin "1") (pinfunction "1_1") (pintype "passive"))
      (node (ref "R42") (pin "2") (pinfunction "2_2") (pintype "passive"))
      (node (ref "X1") (pin "5") (pinfunction "5_5") (pintype "passive"))
    )
    (net (code "35") (name "Net-(C47-Pad1)") (class "Default")
      (node (ref "C47") (pin "1") (pinfunction "1_1") (pintype "passive"))
      (node (ref "R43") (pin "2") (pinfunction "2_2") (pintype "passive"))
      (node (ref "X1") (pin "2") (pinfunction "2_2") (pintype "passive"))
    )
    (net (code "36") (name "Net-(C48-Pad1)") (class "Default")
      (node (ref "C48") (pin "1") (pinfunction "1_1") (pintype "passive"))
      (node (ref "R44") (pin "2") (pinfunction "2_2") (pintype "passive"))
      (node (ref "X2") (pin "2") (pinfunction "2_2") (pintype "passive"))
    )
    (net (code "37") (name "Net-(FB1-Pad2)") (class "Default")
      (node (ref "FB1") (pin "2") (pinfunction "2_2") (pintype "passive"))
      (node (ref "J7") (pin "2") (pinfunction "2_2") (pintype "passive"))
    )
    (net (code "38") (name "Net-(FB2-Pad2)") (class "Default")
      (node (ref "FB2") (pin "2") (pinfunction "2_2") (pintype "passive"))
      (node (ref "J7") (pin "1") (pinfunction "1_1") (pintype "passive"))
    )
    (net (code "39") (name "Net-(R3-Pad1)") (class "Default")
      (node (ref "R3") (pin "1") (pinfunction "1_1") (pintype "passive"))
      (node (ref "U1") (pin "2") (pinfunction "RG_2") (pintype "passive"))
    )
    (net (code "40") (name "Net-(R3-Pad2)") (class "Default")
      (node (ref "R3") (pin "2") (pinfunction "2_2") (pintype "passive"))
      (node (ref "U1") (pin "3") (pinfunction "RG_3") (pintype "passive"))
    )
    (net (code "41") (name "Net-(R6-Pad1)") (class "Default")
      (node (ref "R6") (pin "1") (pinfunction "1_1") (pintype "passive"))
      (node (ref "U2") (pin "2") (pinfunction "RG_2") (pintype "passive"))
    )
    (net (code "42") (name "Net-(R6-Pad2)") (class "Default")
      (node (ref "R6") (pin "2") (pinfunction "2_2") (pintype "passive"))
      (node (ref "U2") (pin "3") (pinfunction "RG_3") (pintype "passive"))
    )
    (net (code "43") (name "Net-(R9-Pad1)") (class "Default")
      (node (ref "R9") (pin "1") (pinfunction "1_1") (pintype "passive"))
      (node (ref "U4") (pin "2") (pinfunction "RG_2") (pintype "passive"))
    )
    (net (code "44") (name "Net-(R9-Pad2)") (class "Default")
      (node (ref "R9") (pin "2") (pinfunction "2_2") (pintype "passive"))
      (node (ref "U4") (pin "3") (pinfunction "RG_3") (pintype "passive"))
    )
    (net (code "45") (name "Net-(R12-Pad1)") (class "Default")
      (node (ref "R12") (pin "1") (pinfunction "1_1") (pintype "passive"))
      (node (ref "U5") (pin "2") (pinfunction "RG_2") (pintype "passive"))
    )
    (net (code "46") (name "Net-(R12-Pad2)") (class "Default")
      (node (ref "R12") (pin "2") (pinfunction "2_2") (pintype "passive"))
      (node (ref "U5") (pin "3") (pinfunction "RG_3") (pintype "passive"))
    )
    (net (code "47") (name "Net-(U1-IN+)") (class "Default")
      (node (ref "C1") (pin "1") (pinfunction "1_1") (pintype "passive"))
      (node (ref "R1") (pin "2") (pinfunction "2_2") (pintype "passive"))
      (node (ref "U1") (pin "4") (pinfunction "IN+_4") (pintype "input"))
    )
    (net (code "48") (name "Net-(U1-IN-)") (class "Default")
      (node (ref "C1") (pin "2") (pinfunction "2_2") (pintype "passive"))
      (node (ref "R2") (pin "2") (pinfunction "2_2") (pintype "passive"))
      (node (ref "U1") (pin "1") (pinfunction "IN-_1") (pintype "input"))
    )
    (net (code "49") (name "Net-(U1-VOUT)") (class "Default")
      (node (ref "C13") (pin "-") (pinfunction "-_-") (pintype "passive"))
      (node (ref "U1") (pin "7") (pinfunction "VOUT_7") (pintype "output"))
    )
    (net (code "50") (name "Net-(U2-IN+)") (class "Default")
      (node (ref "C4") (pin "1") (pinfunction "1_1") (pintype "passive"))
      (node (ref "R4") (pin "2") (pinfunction "2_2") (pintype "passive"))
      (node (ref "U2") (pin "4") (pinfunction "IN+_4") (pintype "input"))
    )
    (net (code "51") (name "Net-(U2-IN-)") (class "Default")
      (node (ref "C4") (pin "2") (pinfunction "2_2") (pintype "passive"))
      (node (ref "R5") (pin "2") (pinfunction "2_2") (pintype "passive"))
      (node (ref "U2") (pin "1") (pinfunction "IN-_1") (pintype "input"))
    )
    (net (code "52") (name "Net-(U2-VOUT)") (class "Default")
      (node (ref "C14") (pin "-") (pinfunction "-_-") (pintype "passive"))
      (node (ref "U2") (pin "7") (pinfunction "VOUT_7") (pintype "output"))
    )
    (net (code "53") (name "Net-(U4-IN+)") (class "Default")
      (node (ref "C7") (pin "1") (pinfunction "1_1") (pintype "passive"))
      (node (ref "R7") (pin "2") (pinfunction "2_2") (pintype "passive"))
      (node (ref "U4") (pin "4") (pinfunction "IN+_4") (pintype "input"))
    )
    (net (code "54") (name "Net-(U4-IN-)") (class "Default")
      (node (ref "C7") (pin "2") (pinfunction "2_2") (pintype "passive"))
      (node (ref "R8") (pin "2") (pinfunction "2_2") (pintype "passive"))
      (node (ref "U4") (pin "1") (pinfunction "IN-_1") (pintype "input"))
    )
    (net (code "55") (name "Net-(U4-VOUT)") (class "Default")
      (node (ref "C15") (pin "-") (pinfunction "-_-") (pintype "passive"))
      (node (ref "U4") (pin "7") (pinfunction "VOUT_7") (pintype "output"))
    )
    (net (code "56") (name "Net-(U5-IN+)") (class "Default")
      (node (ref "C10") (pin "1") (pinfunction "1_1") (pintype "passive"))
      (node (ref "R10") (pin "2") (pinfunction "2_2") (pintype "passive"))
      (node (ref "U5") (pin "4") (pinfunction "IN+_4") (pintype "input"))
    )
    (net (code "57") (name "Net-(U5-IN-)") (class "Default")
      (node (ref "C10") (pin "2") (pinfunction "2_2") (pintype "passive"))
      (node (ref "R11") (pin "2") (pinfunction "2_2") (pintype "passive"))
      (node (ref "U5") (pin "1") (pinfunction "IN-_1") (pintype "input"))
    )
    (net (code "58") (name "Net-(U5-VOUT)") (class "Default")
      (node (ref "C16") (pin "-") (pinfunction "-_-") (pintype "passive"))
      (node (ref "U5") (pin "7") (pinfunction "VOUT_7") (pintype "output"))
    )
    (net (code "59") (name "Net-(U6A--IN)") (class "Default")
      (node (ref "C20") (pin "1") (pinfunction "1_1") (pintype "passive"))
      (node (ref "R13") (pin "2") (pinfunction "2_2") (pintype "passive"))
      (node (ref "R17") (pin "1") (pinfunction "1_1") (pintype "passive"))
      (node (ref "U6") (pin "2") (pinfunction "-IN_2") (pintype "input"))
    )
    (net (code "60") (name "Net-(U6A-OUT)") (class "Default")
      (node (ref "C20") (pin "2") (pinfunction "2_2") (pintype "passive"))
      (node (ref "R17") (pin "2") (pinfunction "2_2") (pintype "passive"))
      (node (ref "R21") (pin "1") (pinfunction "1_1") (pintype "passive"))
      (node (ref "U6") (pin "1") (pinfunction "OUT_1") (pintype "output"))
    )
    (net (code "61") (name "Net-(U6B--IN)") (class "Default")
      (node (ref "C19") (pin "1") (pinfunction "1_1") (pintype "passive"))
      (node (ref "R14") (pin "2") (pinfunction "2_2") (pintype "passive"))
      (node (ref "R18") (pin "1") (pinfunction "1_1") (pintype "passive"))
      (node (ref "U6") (pin "6") (pinfunction "-IN_6") (pintype "input"))
    )
    (net (code "62") (name "Net-(U6B-OUT)") (class "Default")
      (node (ref "C19") (pin "2") (pinfunction "2_2") (pintype "passive"))
      (node (ref "R18") (pin "2") (pinfunction "2_2") (pintype "passive"))
      (node (ref "R22") (pin "1") (pinfunction "1_1") (pintype "passive"))
      (node (ref "U6") (pin "7") (pinfunction "OUT_7") (pintype "output"))
    )
    (net (code "63") (name "Net-(U6C--IN)") (class "Default")
      (node (ref "C17") (pin "1") (pinfunction "1_1") (pintype "passive"))
      (node (ref "R15") (pin "2") (pinfunction "2_2") (pintype "passive"))
      (node (ref "R19") (pin "1") (pinfunction "1_1") (pintype "passive"))
      (node (ref "U6") (pin "9") (pinfunction "-IN_9") (pintype "input"))
    )
    (net (code "64") (name "Net-(U6C-OUT)") (class "Default")
      (node (ref "C17") (pin "2") (pinfunction "2_2") (pintype "passive"))
      (node (ref "R19") (pin "2") (pinfunction "2_2") (pintype "passive"))
      (node (ref "R23") (pin "1") (pinfunction "1_1") (pintype "passive"))
      (node (ref "U6") (pin "8") (pinfunction "OUT_8") (pintype "output"))
    )
    (net (code "65") (name "Net-(U6D--IN)") (class "Default")
      (node (ref "C18") (pin "1") (pinfunction "1_1") (pintype "passive"))
      (node (ref "R16") (pin "2") (pinfunction "2_2") (pintype "passive"))
      (node (ref "R20") (pin "1") (pinfunction "1_1") (pintype "passive"))
      (node (ref "U6") (pin "13") (pinfunction "-IN_13") (pintype "input"))
    )
    (net (code "66") (name "Net-(U6D-OUT)") (class "Default")
      (node (ref "C18") (pin "2") (pinfunction "2_2") (pintype "passive"))
      (node (ref "R20") (pin "2") (pinfunction "2_2") (pintype "passive"))
      (node (ref "R24") (pin "1") (pinfunction "1_1") (pintype "passive"))
      (node (ref "U6") (pin "14") (pinfunction "OUT_14") (pintype "output"))
    )
    (net (code "67") (name "Net-(U7-DOUT)") (class "Default")
      (node (ref "R27") (pin "1") (pinfunction "1_1") (pintype "passive"))
      (node (ref "U7") (pin "9") (pinfunction "DOUT_9") (pintype "output"))
    )
    (net (code "68") (name "Net-(U7-IN1)") (class "Default")
      (node (ref "C9") (pin "1") (pinfunction "1_1") (pintype "passive"))
      (node (ref "R23") (pin "2") (pinfunction "2_2") (pintype "passive"))
      (node (ref "U7") (pin "7") (pinfunction "IN1_7") (pintype "input"))
    )
    (net (code "69") (name "Net-(U7-IN2)") (class "Default")
      (node (ref "C12") (pin "1") (pinfunction "1_1") (pintype "passive"))
      (node (ref "R24") (pin "2") (pinfunction "2_2") (pintype "passive"))
      (node (ref "U7") (pin "6") (pinfunction "IN2_6") (pintype "input"))
    )
    (net (code "70") (name "Net-(U7-IN3)") (class "Default")
      (node (ref "C3") (pin "1") (pinfunction "1_1") (pintype "passive"))
      (node (ref "R21") (pin "2") (pinfunction "2_2") (pintype "passive"))
      (node (ref "U7") (pin "5") (pinfunction "IN3_5") (pintype "input"))
    )
    (net (code "71") (name "Net-(U7-IN4)") (class "Default")
      (node (ref "C6") (pin "1") (pinfunction "1_1") (pintype "passive"))
      (node (ref "R22") (pin "2") (pinfunction "2_2") (pintype "passive"))
      (node (ref "U7") (pin "4") (pinfunction "IN4_4") (pintype "input"))
    )
    (net (code "72") (name "Net-(U8-BYPASS)") (class "Default")
      (node (ref "C28") (pin "1") (pinfunction "1_1") (pintype "passive"))
      (node (ref "U8") (pin "4") (pinfunction "BYPASS_4") (pintype "passive"))
    )
    (net (code "73") (name "Net-(U9A--IN)") (class "Default")
      (node (ref "C33") (pin "1") (pinfunction "1_1") (pintype "passive"))
      (node (ref "R30") (pin "2") (pinfunction "2_2") (pintype "passive"))
      (node (ref "U9") (pin "2") (pinfunction "-IN_2") (pintype "input"))
    )
    (net (code "74") (name "Net-(U9A-OUT)") (class "Default")
      (node (ref "C33") (pin "2") (pinfunction "2_2") (pintype "passive"))
      (node (ref "R31") (pin "2") (pinfunction "2_2") (pintype "passive"))
      (node (ref "R42") (pin "1") (pinfunction "1_1") (pintype "passive"))
      (node (ref "U9") (pin "3") (pinfunction "OUT_3") (pintype "output"))
    )
    (net (code "75") (name "Net-(U9B--IN)") (class "Default")
      (node (ref "C36") (pin "1") (pinfunction "1_1") (pintype "passive"))
      (node (ref "R33") (pin "2") (pinfunction "2_2") (pintype "passive"))
      (node (ref "U9") (pin "13") (pinfunction "-IN_13") (pintype "input"))
    )
    (net (code "76") (name "Net-(U9B-OUT)") (class "Default")
      (node (ref "C36") (pin "2") (pinfunction "2_2") (pintype "passive"))
      (node (ref "R34") (pin "2") (pinfunction "2_2") (pintype "passive"))
      (node (ref "R43") (pin "1") (pinfunction "1_1") (pintype "passive"))
      (node (ref "U9") (pin "12") (pinfunction "OUT_12") (pintype "output"))
    )
    (net (code "77") (name "Net-(U9C-CN)") (class "Default")
      (node (ref "C50") (pin "2") (pinfunction "2_2") (pintype "passive"))
      (node (ref "U9") (pin "7") (pinfunction "CN_7") (pintype "bidirectional"))
    )
    (net (code "78") (name "Net-(U9C-CP)") (class "Default")
      (node (ref "C50") (pin "1") (pinfunction "1_1") (pintype "passive"))
      (node (ref "U9") (pin "8") (pinfunction "CP_8") (pintype "bidirectional"))
    )
    (net (code "79") (name "Net-(U9C-VDD)") (class "Default")
      (node (ref "C51") (pin "1") (pinfunction "1_1") (pintype "passive"))
      (node (ref "C52") (pin "1") (pinfunction "1_1") (pintype "passive"))
      (node (ref "R45") (pin "1") (pinfunction "1_1") (pintype "passive"))
      (node (ref "U9") (pin "5") (pinfunction "~{MUTE}_5") (pintype "input"))
      (node (ref "U9") (pin "9") (pinfunction "VDD_9") (pintype "power_in"))
    )
    (net (code "80") (name "Net-(U9C-VSS)") (class "Default")
      (node (ref "C49") (pin "1") (pinfunction "1_1") (pintype "passive"))
      (node (ref "U9") (pin "6") (pinfunction "VSS_6") (pintype "power_in"))
    )
    (net (code "81") (name "Net-(U10A--IN)") (class "Default")
      (node (ref "C39") (pin "1") (pinfunction "1_1") (pintype "passive"))
      (node (ref "R36") (pin "2") (pinfunction "2_2") (pintype "passive"))
      (node (ref "U10") (pin "2") (pinfunction "-IN_2") (pintype "input"))
    )
    (net (code "82") (name "Net-(U10A-OUT)") (class "Default")
      (node (ref "C39") (pin "2") (pinfunction "2_2") (pintype "passive"))
      (node (ref "R37") (pin "2") (pinfunction "2_2") (pintype "passive"))
      (node (ref "R41") (pin "1") (pinfunction "1_1") (pintype "passive"))
      (node (ref "U10") (pin "3") (pinfunction "OUT_3") (pintype "output"))
    )
    (net (code "83") (name "Net-(U10B--IN)") (class "Default")
      (node (ref "C42") (pin "1") (pinfunction "1_1") (pintype "passive"))
      (node (ref "R39") (pin "2") (pinfunction "2_2") (pintype "passive"))
      (node (ref "U10") (pin "13") (pinfunction "-IN_13") (pintype "input"))
    )
    (net (code "84") (name "Net-(U10B-OUT)") (class "Default")
      (node (ref "C42") (pin "2") (pinfunction "2_2") (pintype "passive"))
      (node (ref "R40") (pin "2") (pinfunction "2_2") (pintype "passive"))
      (node (ref "R44") (pin "1") (pinfunction "1_1") (pintype "passive"))
      (node (ref "U10") (pin "12") (pinfunction "OUT_12") (pintype "output"))
    )
    (net (code "85") (name "Net-(U10C-CN)") (class "Default")
      (node (ref "C54") (pin "2") (pinfunction "2_2") (pintype "passive"))
      (node (ref "U10") (pin "7") (pinfunction "CN_7") (pintype "bidirectional"))
    )
    (net (code "86") (name "Net-(U10C-CP)") (class "Default")
      (node (ref "C54") (pin "1") (pinfunction "1_1") (pintype "passive"))
      (node (ref "U10") (pin "8") (pinfunction "CP_8") (pintype "bidirectional"))
    )
    (net (code "87") (name "Net-(U10C-VDD)") (class "Default")
      (node (ref "C55") (pin "1") (pinfunction "1_1") (pintype "passive"))
      (node (ref "C56") (pin "1") (pinfunction "1_1") (pintype "passive"))
      (node (ref "R47") (pin "1") (pinfunction "1_1") (pintype "passive"))
      (node (ref "U10") (pin "5") (pinfunction "~{MUTE}_5") (pintype "input"))
      (node (ref "U10") (pin "9") (pinfunction "VDD_9") (pintype "power_in"))
    )
    (net (code "88") (name "Net-(U10C-VSS)") (class "Default")
      (node (ref "C53") (pin "1") (pinfunction "1_1") (pintype "passive"))
      (node (ref "U10") (pin "6") (pinfunction "VSS_6") (pintype "power_in"))
    )
    (net (code "89") (name "Net-(U12-CAP+)") (class "Default")
      (node (ref "C63") (pin "1") (pinfunction "1_1") (pintype "passive"))
      (node (ref "U12") (pin "1") (pinfunction "CAP+_1") (pintype "passive"))
    )
    (net (code "90") (name "Net-(U12-CAP-)") (class "Default")
      (node (ref "C63") (pin "2") (pinfunction "2_2") (pintype "passive"))
      (node (ref "U12") (pin "3") (pinfunction "CAP-_3") (pintype "passive"))
    )
    (net (code "91") (name "Net-(U12-VFB)") (class "Default")
      (node (ref "R49") (pin "1") (pinfunction "1_1") (pintype "passive"))
      (node (ref "R50") (pin "2") (pinfunction "2_2") (pintype "passive"))
      (node (ref "U12") (pin "6") (pinfunction "VFB_6") (pintype "passive"))
    )
    (net (code "92") (name "Net-(U12-VIN)") (class "Default")
      (node (ref "C64") (pin "1") (pinfunction "1_1") (pintype "passive"))
      (node (ref "C66") (pin "1") (pinfunction "1_1") (pintype "passive"))
      (node (ref "R51") (pin "2") (pinfunction "2_2") (pintype "passive"))
      (node (ref "U12") (pin "4") (pinfunction "~{SD}_4") (pintype "passive"))
      (node (ref "U12") (pin "8") (pinfunction "VIN_8") (pintype "input"))
    )
    (net (code "93") (name "Net-(U12-VNEG)") (class "Default")
      (node (ref "C32") (pin "1") (pinfunction "1_1") (pintype "passive"))
      (node (ref "U12") (pin "5") (pinfunction "VNEG_5") (pintype "passive"))
    )
    (net (code "94") (name "SCLK") (class "Default")
      (node (ref "J6") (pin "4") (pinfunction "4_4") (pintype "passive"))
      (node (ref "U11") (pin "10") (pinfunction "SCLK_10") (pintype "input"))
      (node (ref "U7") (pin "10") (pinfunction "SCLK_10") (pintype "passive"))
    )
    (net (code "95") (name "V_BATT") (class "Default")
      (node (ref "C26") (pin "1") (pinfunction "1_1") (pintype "passive"))
      (node (ref "C29") (pin "1") (pinfunction "1_1") (pintype "passive"))
      (node (ref "C30") (pin "+") (pinfunction "+_+") (pintype "passive"))
      (node (ref "FB2") (pin "1") (pinfunction "1_1") (pintype "passive"))
      (node (ref "U8") (pin "1") (pinfunction "VIN_1") (pintype "input"))
      (node (ref "U8") (pin "3") (pinfunction "ON/~{OFF}_3") (pintype "passive"))
    )
    (net (code "96") (name "unconnected-(U9C-UVP-Pad11)") (class "Default")
      (node (ref "U9") (pin "11") (pinfunction "UVP_11") (pintype "input"))
    )
    (net (code "97") (name "unconnected-(U10C-UVP-Pad11)") (class "Default")
      (node (ref "U10") (pin "11") (pinfunction "UVP_11") (pintype "input"))
    )
    (net (code "98") (name "unconnected-(X1-Pad3)") (class "Default")
      (node (ref "X1") (pin "3") (pinfunction "3_3") (pintype "passive"))
    )
    (net (code "99") (name "unconnected-(X1-Pad4)") (class "Default")
      (node (ref "X1") (pin "4") (pinfunction "4_4") (pintype "passive"))
    )
    (net (code "100") (name "unconnected-(X2-Pad3)") (class "Default")
      (node (ref "X2") (pin "3") (pinfunction "3_3") (pintype "passive"))
    )
    (net (code "101") (name "unconnected-(X2-Pad4)") (class "Default")
      (node (ref "X2") (pin "4") (pinfunction "4_4") (pintype "passive"))
    )
  )
)
